# Switch_Board_for_PC-11491_Joystick_Proje.net
KiCad netlist of a schematic drawn in EAGLE
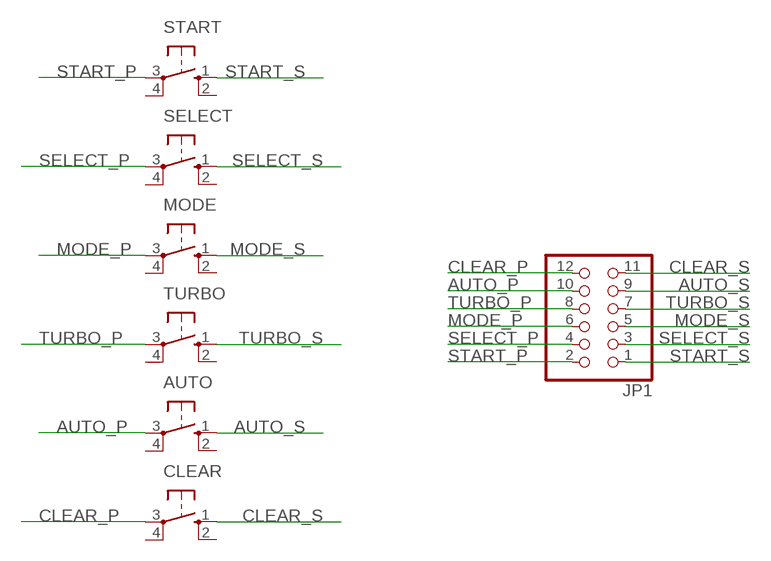
[diagram p0: schematic, sheet 1]

(export (version "E")
  (design (tool "Eeschema 10.0.6"))
  (components
    (comp (ref "AUTO")
      (value "10-XX")
      (footprint "eagle-import:B3F-10XX")
      (fields (field (name "MPN") "B3F-1000"))
      (libsource (lib "eagle-import") (part "10-XX"))
    )
    (comp (ref "CLEAR")
      (value "10-XX")
      (footprint "eagle-import:B3F-10XX")
      (fields (field (name "MPN") "B3F-1000"))
      (libsource (lib "eagle-import") (part "10-XX"))
    )
    (comp (ref "JP1")
      (value "PINHD-2X6")
      (footprint "eagle-import:2X06")
      (libsource (lib "eagle-import") (part "PINHD-2X6"))
    )
    (comp (ref "MODE")
      (value "10-XX")
      (footprint "eagle-import:B3F-10XX")
      (fields (field (name "MPN") "B3F-1000"))
      (libsource (lib "eagle-import") (part "10-XX"))
    )
    (comp (ref "SELECT")
      (value "10-XX")
      (footprint "eagle-import:B3F-10XX")
      (fields (field (name "MPN") "B3F-1000"))
      (libsource (lib "eagle-import") (part "10-XX"))
    )
    (comp (ref "START")
      (value "10-XX")
      (footprint "eagle-import:B3F-10XX")
      (fields (field (name "MPN") "B3F-1000"))
      (libsource (lib "eagle-import") (part "10-XX"))
    )
    (comp (ref "TURBO")
      (value "10-XX")
      (footprint "eagle-import:B3F-10XX")
      (fields (field (name "MPN") "B3F-1000"))
      (libsource (lib "eagle-import") (part "10-XX"))
    )
  )
  (nets
    (net (code "1") (name "/AUTO_P") (class "Default")
      (node (ref "AUTO") (pin "3") (pinfunction "P_3") (pintype "passive"))
      (node (ref "JP1") (pin "10") (pinfunction "10_10") (pintype "passive"))
    )
    (net (code "2") (name "/AUTO_S") (class "Default")
      (node (ref "AUTO") (pin "1") (pinfunction "S_1") (pintype "passive"))
      (node (ref "JP1") (pin "9") (pinfunction "9_9") (pintype "passive"))
    )
    (net (code "3") (name "/CLEAR_P") (class "Default")
      (node (ref "CLEAR") (pin "3") (pinfunction "P_3") (pintype "passive"))
      (node (ref "JP1") (pin "12") (pinfunction "12_12") (pintype "passive"))
    )
    (net (code "4") (name "/CLEAR_S") (class "Default")
      (node (ref "CLEAR") (pin "1") (pinfunction "S_1") (pintype "passive"))
      (node (ref "JP1") (pin "11") (pinfunction "11_11") (pintype "passive"))
    )
    (net (code "5") (name "/MODE_P") (class "Default")
      (node (ref "JP1") (pin "6") (pinfunction "6_6") (pintype "passive"))
      (node (ref "MODE") (pin "3") (pinfunction "P_3") (pintype "passive"))
    )
    (net (code "6") (name "/MODE_S") (class "Default")
      (node (ref "JP1") (pin "5") (pinfunction "5_5") (pintype "passive"))
      (node (ref "MODE") (pin "1") (pinfunction "S_1") (pintype "passive"))
    )
    (net (code "7") (name "/SELECT_P") (class "Default")
      (node (ref "JP1") (pin "4") (pinfunction "4_4") (pintype "passive"))
      (node (ref "SELECT") (pin "3") (pinfunction "P_3") (pintype "passive"))
    )
    (net (code "8") (name "/SELECT_S") (class "Default")
      (node (ref "JP1") (pin "3") (pinfunction "3_3") (pintype "passive"))
      (node (ref "SELECT") (pin "1") (pinfunction "S_1") (pintype "passive"))
    )
    (net (code "9") (name "/START_P") (class "Default")
      (node (ref "JP1") (pin "2") (pinfunction "2_2") (pintype "passive"))
      (node (ref "START") (pin "3") (pinfunction "P_3") (pintype "passive"))
    )
    (net (code "10") (name "/START_S") (class "Default")
      (node (ref "JP1") (pin "1") (pinfunction "1_1") (pintype "passive"))
      (node (ref "START") (pin "1") (pinfunction "S_1") (pintype "passive"))
    )
    (net (code "11") (name "/TURBO_P") (class "Default")
      (node (ref "JP1") (pin "8") (pinfunction "8_8") (pintype "passive"))
      (node (ref "TURBO") (pin "3") (pinfunction "P_3") (pintype "passive"))
    )
    (net (code "12") (name "/TURBO_S") (class "Default")
      (node (ref "JP1") (pin "7") (pinfunction "7_7") (pintype "passive"))
      (node (ref "TURBO") (pin "1") (pinfunction "S_1") (pintype "passive"))
    )
    (net (code "13") (name "unconnected-(AUTO-P1-Pad4)") (class "Default")
      (node (ref "AUTO") (pin "4") (pinfunction "P1_4") (pintype "passive"))
    )
    (net (code "14") (name "unconnected-(AUTO-S1-Pad2)") (class "Default")
      (node (ref "AUTO") (pin "2") (pinfunction "S1_2") (pintype "passive"))
    )
    (net (code "15") (name "unconnected-(CLEAR-P1-Pad4)") (class "Default")
      (node (ref "CLEAR") (pin "4") (pinfunction "P1_4") (pintype "passive"))
    )
    (net (code "16") (name "unconnected-(CLEAR-S1-Pad2)") (class "Default")
      (node (ref "CLEAR") (pin "2") (pinfunction "S1_2") (pintype "passive"))
    )
    (net (code "17") (name "unconnected-(MODE-P1-Pad4)") (class "Default")
      (node (ref "MODE") (pin "4") (pinfunction "P1_4") (pintype "passive"))
    )
    (net (code "18") (name "unconnected-(MODE-S1-Pad2)") (class "Default")
      (node (ref "MODE") (pin "2") (pinfunction "S1_2") (pintype "passive"))
    )
    (net (code "19") (name "unconnected-(SELECT-P1-Pad4)") (class "Default")
      (node (ref "SELECT") (pin "4") (pinfunction "P1_4") (pintype "passive"))
    )
    (net (code "20") (name "unconnected-(SELECT-S1-Pad2)") (class "Default")
      (node (ref "SELECT") (pin "2") (pinfunction "S1_2") (pintype "passive"))
    )
    (net (code "21") (name "unconnected-(START-P1-Pad4)") (class "Default")
      (node (ref "START") (pin "4") (pinfunction "P1_4") (pintype "passive"))
    )
    (net (code "22") (name "unconnected-(START-S1-Pad2)") (class "Default")
      (node (ref "START") (pin "2") (pinfunction "S1_2") (pintype "passive"))
    )
    (net (code "23") (name "unconnected-(TURBO-P1-Pad4)") (class "Default")
      (node (ref "TURBO") (pin "4") (pinfunction "P1_4") (pintype "passive"))
    )
    (net (code "24") (name "unconnected-(TURBO-S1-Pad2)") (class "Default")
      (node (ref "TURBO") (pin "2") (pinfunction "S1_2") (pintype "passive"))
    )
  )
)
